# S7CAS-PLEIADES-CARTE-MERE_Pxx_PHY.net
KiCad netlist of a schematic drawn in Altium Designer
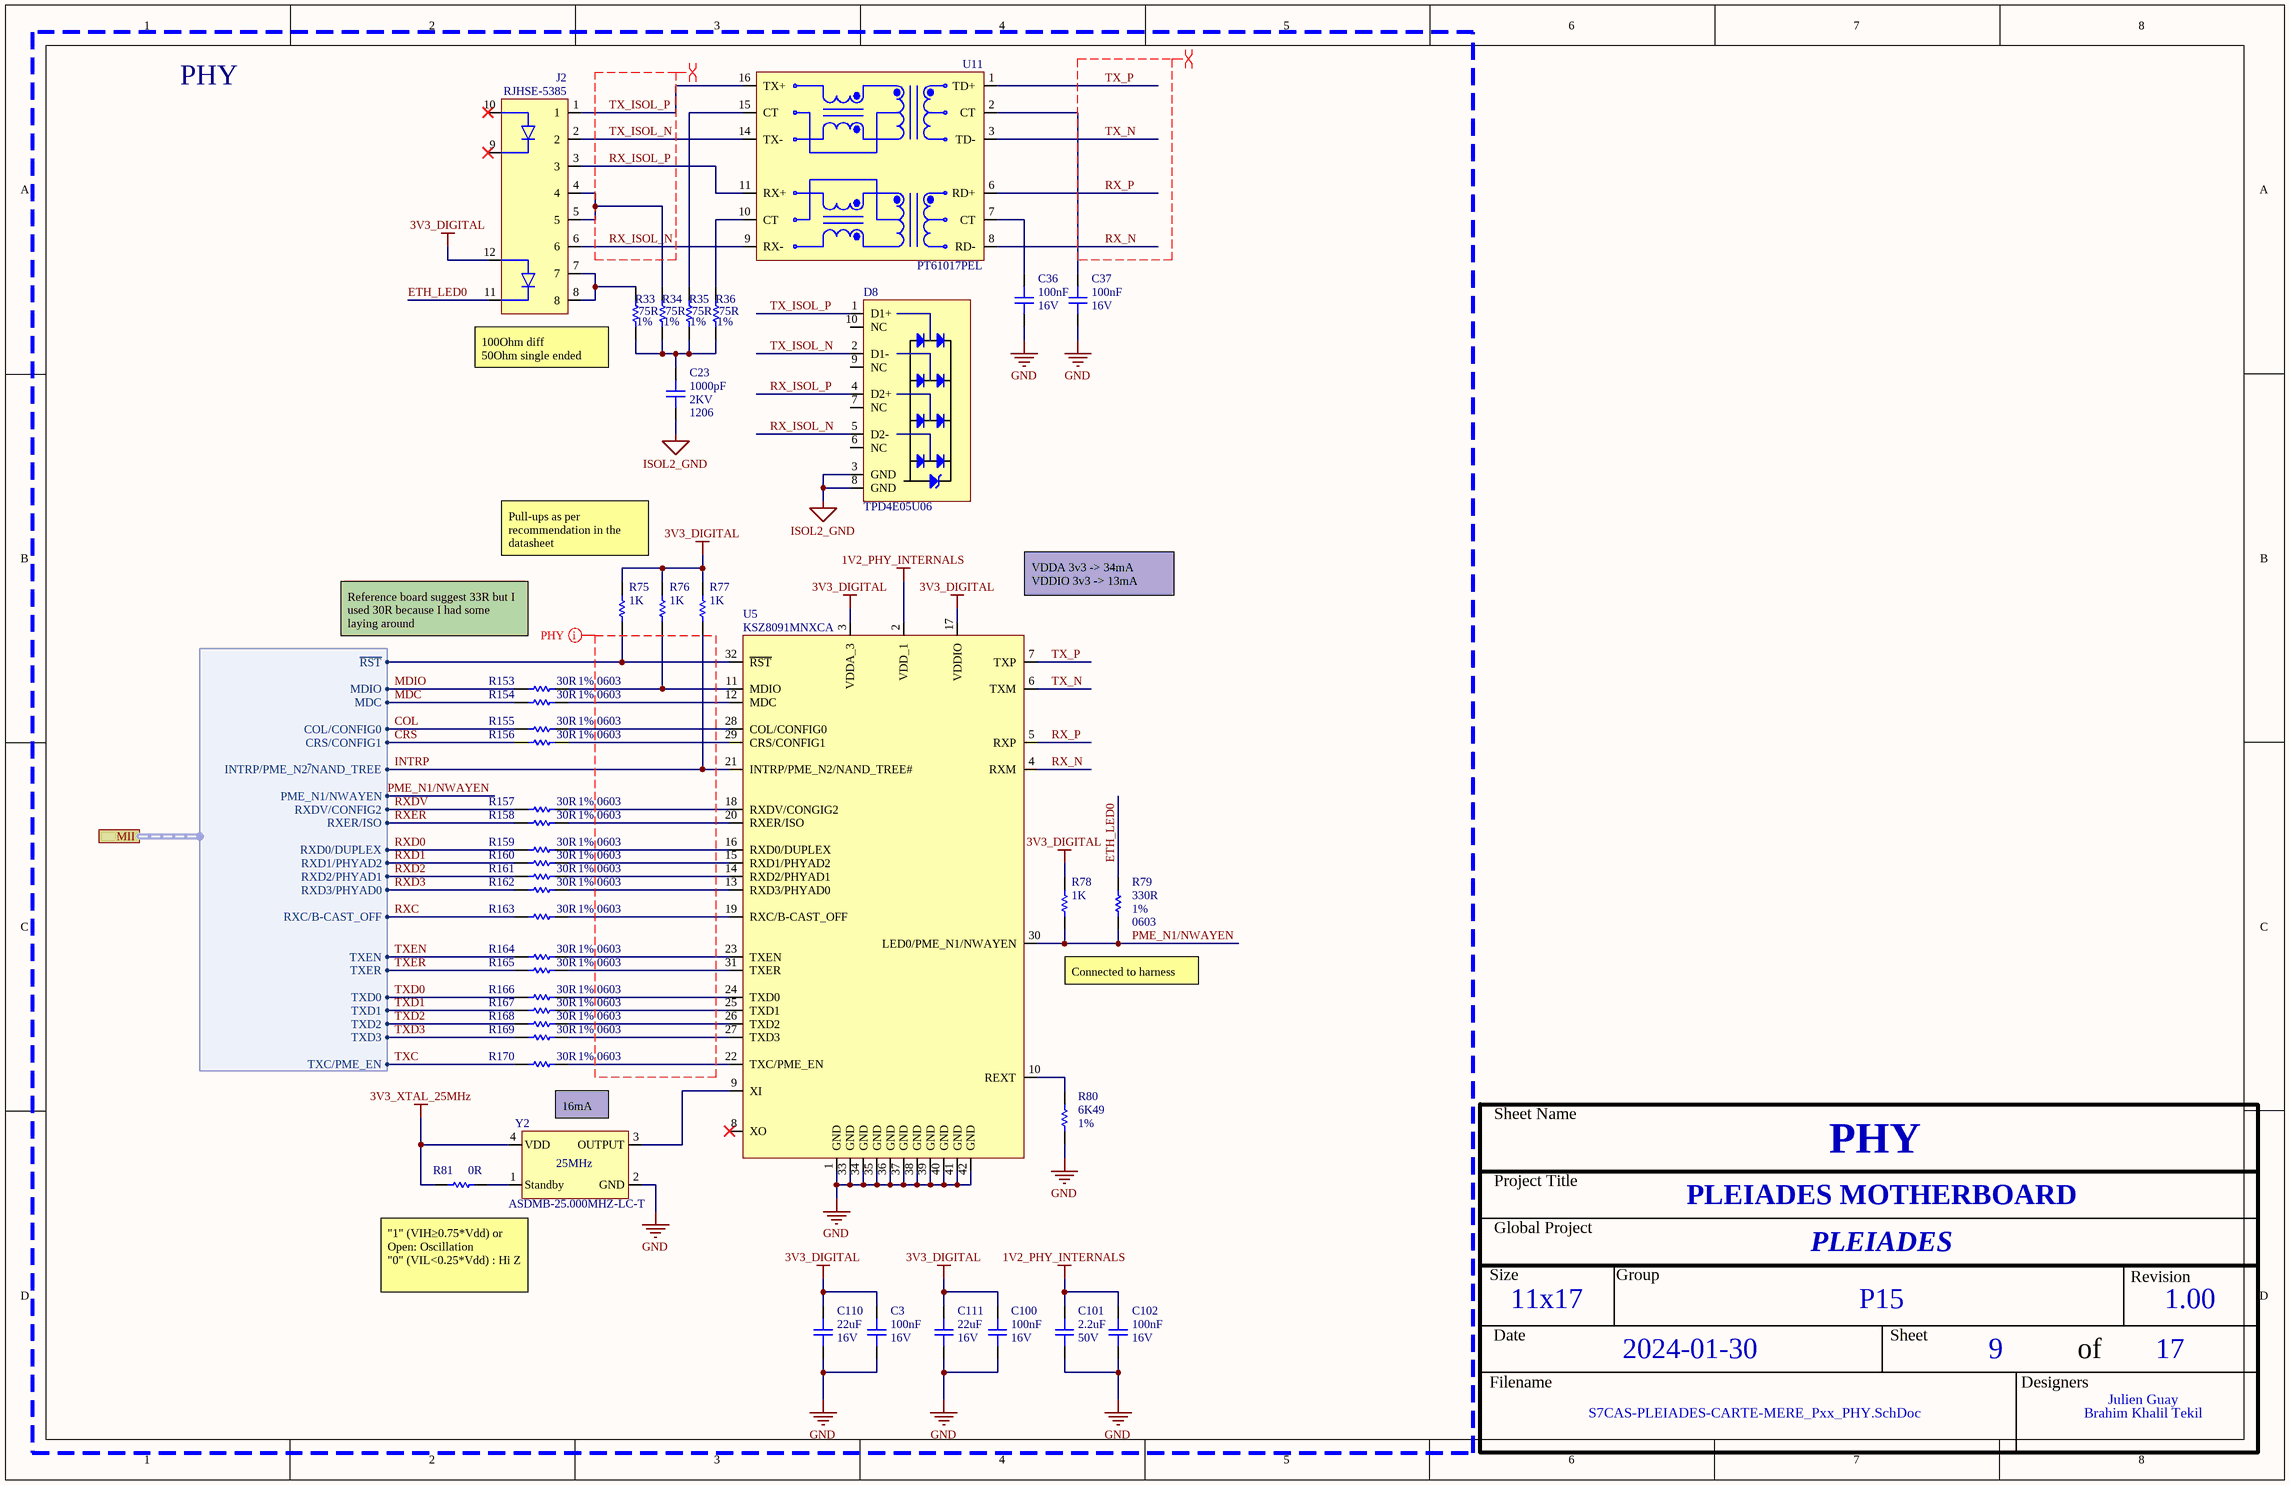
[diagram p0: S7CAS-PLEIADES-CARTE-MERE_Pxx_PHY.SchDoc]

(export (version "E")
  (design (tool "Eeschema 10.0.6"))
  (components
    (comp (ref "C3")
      (value "100nF")
      (footprint "CAP_0603")
      (description "CAP - 0603")
      (fields (field (name "VOLTAGE") "16V") (field (name "CREATEDBY") "Jonathan Bouchard"))
      (libsource (lib "S7CAS_LIB2023") (part "CAP - 0603"))
    )
    (comp (ref "C23")
      (value "1000pF")
      (footprint "CAP_1206")
      (description "CAP - 1206")
      (fields
        (field (name "VOLTAGE") "2KV")
        (field (name "PACKAGE") "1206")
        (field (name "CREATEDBY") "Jonathan Bouchard")
      )
      (libsource (lib "S7CAS_LIB2023") (part "CAP - 1206"))
    )
    (comp (ref "C36")
      (value "100nF")
      (footprint "CAP_0603")
      (description "CAP - 0603")
      (fields (field (name "VOLTAGE") "16V") (field (name "CREATEDBY") "Jonathan Bouchard"))
      (libsource (lib "S7CAS_LIB2023") (part "CAP - 0603"))
    )
    (comp (ref "C37")
      (value "100nF")
      (footprint "CAP_0603")
      (description "CAP - 0603")
      (fields (field (name "VOLTAGE") "16V") (field (name "CREATEDBY") "Jonathan Bouchard"))
      (libsource (lib "S7CAS_LIB2023") (part "CAP - 0603"))
    )
    (comp (ref "C100")
      (value "100nF")
      (footprint "CAP_0603")
      (description "CAP - 0603")
      (fields (field (name "VOLTAGE") "16V") (field (name "CREATEDBY") "Jonathan Bouchard"))
      (libsource (lib "S7CAS_LIB2023") (part "CAP - 0603"))
    )
    (comp (ref "C101")
      (value "2.2uF")
      (footprint "CAP_0603")
      (description "CAP - 0603")
      (fields (field (name "VOLTAGE") "50V") (field (name "CREATEDBY") "Jonathan Bouchard"))
      (libsource (lib "S7CAS_LIB2023") (part "CAP - 0603"))
    )
    (comp (ref "C102")
      (value "100nF")
      (footprint "CAP_0603")
      (description "CAP - 0603")
      (fields (field (name "VOLTAGE") "16V") (field (name "CREATEDBY") "Jonathan Bouchard"))
      (libsource (lib "S7CAS_LIB2023") (part "CAP - 0603"))
    )
    (comp (ref "C110")
      (value "22uF")
      (footprint "CAP_1206")
      (description "CAP - 1206")
      (fields (field (name "VOLTAGE") "16V") (field (name "CREATEDBY") "Jonathan Bouchard"))
      (libsource (lib "S7CAS_LIB2023") (part "CAP - 1206"))
    )
    (comp (ref "C111")
      (value "22uF")
      (footprint "CAP_1206")
      (description "CAP - 1206")
      (fields (field (name "VOLTAGE") "16V") (field (name "CREATEDBY") "Jonathan Bouchard"))
      (libsource (lib "S7CAS_LIB2023") (part "CAP - 1206"))
    )
    (comp (ref "D8")
      (value "TPD4E05U06")
      (footprint "TVS_DATA_TPD4E05U06")
      (description "TVS - TVS DIODE 5.5VWM 14VC - 10SON")
      (fields
        (field (name "CREATEDBY/DATE") "Olivier Bernard / 12/3/2018")
        (field (name "VERIFIEDBY") "Caroline Paulin / 4 juillet 2018")
      )
      (libsource (lib "S7CAS_LIB2023") (part "TVS_DATA_TPD4E05U06"))
    )
    (comp (ref "J2")
      (value "RJHSE-5385")
      (footprint "CONN_ETHERNET_RJHSE-5385")
      (description "CONN - MOD JACK RJ45 R/A ETHERNET - TH")
      (fields (field (name "MFG") "Amphenol") (field (name "CREATEDBY") "Jonathan Bouchard"))
      (libsource (lib "S7CAS_LIB2023") (part "CONN_ETHERNET_RJHSE-5385"))
    )
    (comp (ref "R33")
      (value "75R")
      (footprint "RES_0603")
      (description "RES - 0603")
      (fields (field (name "PRECISION") "1%") (field (name "CREATEDBY") "Jonathan Bouchard"))
      (libsource (lib "S7CAS_LIB2023") (part "RES - 0603"))
    )
    (comp (ref "R34")
      (value "75R")
      (footprint "RES_0603")
      (description "RES - 0603")
      (fields (field (name "PRECISION") "1%") (field (name "CREATEDBY") "Jonathan Bouchard"))
      (libsource (lib "S7CAS_LIB2023") (part "RES - 0603"))
    )
    (comp (ref "R35")
      (value "75R")
      (footprint "RES_0603")
      (description "RES - 0603")
      (fields (field (name "PRECISION") "1%") (field (name "CREATEDBY") "Jonathan Bouchard"))
      (libsource (lib "S7CAS_LIB2023") (part "RES - 0603"))
    )
    (comp (ref "R36")
      (value "75R")
      (footprint "RES_0603")
      (description "RES - 0603")
      (fields (field (name "PRECISION") "1%") (field (name "CREATEDBY") "Jonathan Bouchard"))
      (libsource (lib "S7CAS_LIB2023") (part "RES - 0603"))
    )
    (comp (ref "R75")
      (value "1K")
      (footprint "RES_0603")
      (description "RES - 0603")
      (fields (field (name "CREATEDBY") "Jonathan Bouchard"))
      (libsource (lib "S7CAS_LIB2023") (part "RES - 0603"))
    )
    (comp (ref "R76")
      (value "1K")
      (footprint "RES_0603")
      (description "RES - 0603")
      (fields (field (name "CREATEDBY") "Jonathan Bouchard"))
      (libsource (lib "S7CAS_LIB2023") (part "RES - 0603"))
    )
    (comp (ref "R77")
      (value "1K")
      (footprint "RES_0603")
      (description "RES - 0603")
      (fields (field (name "CREATEDBY") "Jonathan Bouchard"))
      (libsource (lib "S7CAS_LIB2023") (part "RES - 0603"))
    )
    (comp (ref "R78")
      (value "1K")
      (footprint "RES_0603")
      (description "RES - 0603")
      (fields (field (name "CREATEDBY") "Jonathan Bouchard"))
      (libsource (lib "S7CAS_LIB2023") (part "RES - 0603"))
    )
    (comp (ref "R79")
      (value "330R")
      (footprint "RES_0603")
      (description "RES - 0603")
      (fields
        (field (name "PACKAGE") "0603")
        (field (name "PRECISION") "1%")
        (field (name "CREATEDBY") "Jonathan Bouchard")
      )
      (libsource (lib "S7CAS_LIB2023") (part "RES - 0603"))
    )
    (comp (ref "R80")
      (value "6K49")
      (footprint "RES_0402")
      (description "RES - 0402")
      (fields
        (field (name "VOLTAGE") "50V")
        (field (name "POWER") "1/16W")
        (field (name "PRECISION") "1%")
        (field (name "CREATEDBY") "Jonathan Bouchard")
      )
      (libsource (lib "S7CAS_LIB2023") (part "RES - 0402"))
    )
    (comp (ref "R81")
      (value "0R")
      (footprint "RES_0603")
      (description "RES - 0603")
      (fields (field (name "CREATEDBY") "Jonathan Bouchard"))
      (libsource (lib "S7CAS_LIB2023") (part "RES - 0603"))
    )
    (comp (ref "R153")
      (value "30R")
      (footprint "RES_0603")
      (description "RES - 0603")
      (fields
        (field (name "PACKAGE") "0603")
        (field (name "PRECISION") "1%")
        (field (name "CREATEDBY") "Jonathan Bouchard")
      )
      (libsource (lib "S7CAS_LIB2023") (part "RES - 0603"))
    )
    (comp (ref "R154")
      (value "30R")
      (footprint "RES_0603")
      (description "RES - 0603")
      (fields
        (field (name "PACKAGE") "0603")
        (field (name "PRECISION") "1%")
        (field (name "CREATEDBY") "Jonathan Bouchard")
      )
      (libsource (lib "S7CAS_LIB2023") (part "RES - 0603"))
    )
    (comp (ref "R155")
      (value "30R")
      (footprint "RES_0603")
      (description "RES - 0603")
      (fields
        (field (name "PACKAGE") "0603")
        (field (name "PRECISION") "1%")
        (field (name "CREATEDBY") "Jonathan Bouchard")
      )
      (libsource (lib "S7CAS_LIB2023") (part "RES - 0603"))
    )
    (comp (ref "R156")
      (value "30R")
      (footprint "RES_0603")
      (description "RES - 0603")
      (fields
        (field (name "PACKAGE") "0603")
        (field (name "PRECISION") "1%")
        (field (name "CREATEDBY") "Jonathan Bouchard")
      )
      (libsource (lib "S7CAS_LIB2023") (part "RES - 0603"))
    )
    (comp (ref "R157")
      (value "30R")
      (footprint "RES_0603")
      (description "RES - 0603")
      (fields
        (field (name "PACKAGE") "0603")
        (field (name "PRECISION") "1%")
        (field (name "CREATEDBY") "Jonathan Bouchard")
      )
      (libsource (lib "S7CAS_LIB2023") (part "RES - 0603"))
    )
    (comp (ref "R158")
      (value "30R")
      (footprint "RES_0603")
      (description "RES - 0603")
      (fields
        (field (name "PACKAGE") "0603")
        (field (name "PRECISION") "1%")
        (field (name "CREATEDBY") "Jonathan Bouchard")
      )
      (libsource (lib "S7CAS_LIB2023") (part "RES - 0603"))
    )
    (comp (ref "R159")
      (value "30R")
      (footprint "RES_0603")
      (description "RES - 0603")
      (fields
        (field (name "PACKAGE") "0603")
        (field (name "PRECISION") "1%")
        (field (name "CREATEDBY") "Jonathan Bouchard")
      )
      (libsource (lib "S7CAS_LIB2023") (part "RES - 0603"))
    )
    (comp (ref "R160")
      (value "30R")
      (footprint "RES_0603")
      (description "RES - 0603")
      (fields
        (field (name "PACKAGE") "0603")
        (field (name "PRECISION") "1%")
        (field (name "CREATEDBY") "Jonathan Bouchard")
      )
      (libsource (lib "S7CAS_LIB2023") (part "RES - 0603"))
    )
    (comp (ref "R161")
      (value "30R")
      (footprint "RES_0603")
      (description "RES - 0603")
      (fields
        (field (name "PACKAGE") "0603")
        (field (name "PRECISION") "1%")
        (field (name "CREATEDBY") "Jonathan Bouchard")
      )
      (libsource (lib "S7CAS_LIB2023") (part "RES - 0603"))
    )
    (comp (ref "R162")
      (value "30R")
      (footprint "RES_0603")
      (description "RES - 0603")
      (fields
        (field (name "PACKAGE") "0603")
        (field (name "PRECISION") "1%")
        (field (name "CREATEDBY") "Jonathan Bouchard")
      )
      (libsource (lib "S7CAS_LIB2023") (part "RES - 0603"))
    )
    (comp (ref "R163")
      (value "30R")
      (footprint "RES_0603")
      (description "RES - 0603")
      (fields
        (field (name "PACKAGE") "0603")
        (field (name "PRECISION") "1%")
        (field (name "CREATEDBY") "Jonathan Bouchard")
      )
      (libsource (lib "S7CAS_LIB2023") (part "RES - 0603"))
    )
    (comp (ref "R164")
      (value "30R")
      (footprint "RES_0603")
      (description "RES - 0603")
      (fields
        (field (name "PACKAGE") "0603")
        (field (name "PRECISION") "1%")
        (field (name "CREATEDBY") "Jonathan Bouchard")
      )
      (libsource (lib "S7CAS_LIB2023") (part "RES - 0603"))
    )
    (comp (ref "R165")
      (value "30R")
      (footprint "RES_0603")
      (description "RES - 0603")
      (fields
        (field (name "PACKAGE") "0603")
        (field (name "PRECISION") "1%")
        (field (name "CREATEDBY") "Jonathan Bouchard")
      )
      (libsource (lib "S7CAS_LIB2023") (part "RES - 0603"))
    )
    (comp (ref "R166")
      (value "30R")
      (footprint "RES_0603")
      (description "RES - 0603")
      (fields
        (field (name "PACKAGE") "0603")
        (field (name "PRECISION") "1%")
        (field (name "CREATEDBY") "Jonathan Bouchard")
      )
      (libsource (lib "S7CAS_LIB2023") (part "RES - 0603"))
    )
    (comp (ref "R167")
      (value "30R")
      (footprint "RES_0603")
      (description "RES - 0603")
      (fields
        (field (name "PACKAGE") "0603")
        (field (name "PRECISION") "1%")
        (field (name "CREATEDBY") "Jonathan Bouchard")
      )
      (libsource (lib "S7CAS_LIB2023") (part "RES - 0603"))
    )
    (comp (ref "R168")
      (value "30R")
      (footprint "RES_0603")
      (description "RES - 0603")
      (fields
        (field (name "PACKAGE") "0603")
        (field (name "PRECISION") "1%")
        (field (name "CREATEDBY") "Jonathan Bouchard")
      )
      (libsource (lib "S7CAS_LIB2023") (part "RES - 0603"))
    )
    (comp (ref "R169")
      (value "30R")
      (footprint "RES_0603")
      (description "RES - 0603")
      (fields
        (field (name "PACKAGE") "0603")
        (field (name "PRECISION") "1%")
        (field (name "CREATEDBY") "Jonathan Bouchard")
      )
      (libsource (lib "S7CAS_LIB2023") (part "RES - 0603"))
    )
    (comp (ref "R170")
      (value "30R")
      (footprint "RES_0603")
      (description "RES - 0603")
      (fields
        (field (name "PACKAGE") "0603")
        (field (name "PRECISION") "1%")
        (field (name "CREATEDBY") "Jonathan Bouchard")
      )
      (libsource (lib "S7CAS_LIB2023") (part "RES - 0603"))
    )
    (comp (ref "U5")
      (value "KSZ8091MNXCA")
      (footprint "COM_ETH_PHY_KSZ8091MNXCA")
      (description "COM - ETHERNET PHY 10/100 - QFN-32")
      (fields
        (field (name "VOLTAGE") "1.8V, 2.5V, 3.3V")
        (field (name "MFG") "Micrel")
        (field (name "CREATEDBY") "Jonathan Bouchard")
      )
      (libsource (lib "S7CAS_LIB2023") (part "COM_ETH_PHY_KSZ8091MNXCA"))
    )
    (comp (ref "U11")
      (value "PT61017PEL")
      (footprint "ISO_PT61017PEL")
      (description "ISO - 350µH LAN 10/100 Base-T Pulse Transformer 1CT:1CT Surface Mount")
      (libsource (lib "S7CAS_LIB2023") (part "ISO_PT61017PEL"))
    )
    (comp (ref "Y2")
      (value "ASDMB-25.000MHZ-LC-T")
      (footprint "OSC_ASDMB-25.000MHZ-LC-T")
      (description "OSC - 25MHz XO (Standard) LVCMOS - 4-SMD, No Lead")
      (fields
        (field (name "TOLERANCE") "±50ppm")
        (field (name "CREATEDBY/DATE") "Joël Lemay 2019-03-29")
        (field (name "VERIFIEDBY") "C. Paulin - 29 mai 2019")
      )
      (libsource (lib "S7CAS_LIB2023") (part "OSC_ASDMB-25.000MHZ-LC-T"))
    )
  )
  (nets
    (net (code "4") (name "/COL") (class "Default")
      (node (ref "R155") (pin "1") (pinfunction "1_1") (pintype "passive"))
    )
    (net (code "5") (name "/CRS") (class "Default")
      (node (ref "R156") (pin "1") (pinfunction "1_1") (pintype "passive"))
    )
    (net (code "6") (name "/ETH_LED0") (class "Default")
      (node (ref "J2") (pin "11") (pinfunction "LED2_K_11") (pintype "passive"))
      (node (ref "R79") (pin "2") (pinfunction "2_2") (pintype "passive"))
    )
    (net (code "7") (name "/INTRP") (class "Default")
      (node (ref "R77") (pin "1") (pinfunction "1_1") (pintype "passive"))
      (node (ref "U5") (pin "21") (pinfunction "INTRP/PME_N2/NAND_TREE#_21") (pintype "passive"))
    )
    (net (code "8") (name "/MDC") (class "Default")
      (node (ref "R154") (pin "1") (pinfunction "1_1") (pintype "passive"))
    )
    (net (code "9") (name "/MDIO") (class "Default")
      (node (ref "R153") (pin "1") (pinfunction "1_1") (pintype "passive"))
    )
    (net (code "10") (name "/PME_N1{slash}NWAYEN") (class "Default")
      (node (ref "R78") (pin "1") (pinfunction "1_1") (pintype "passive"))
      (node (ref "R79") (pin "1") (pinfunction "1_1") (pintype "passive"))
      (node (ref "U5") (pin "30") (pinfunction "LED0/PME_N1/NWAYEN_30") (pintype "passive"))
    )
    (net (code "11") (name "/RXC") (class "Default")
      (node (ref "R163") (pin "1") (pinfunction "1_1") (pintype "passive"))
    )
    (net (code "12") (name "/RXD0") (class "Default")
      (node (ref "R159") (pin "1") (pinfunction "1_1") (pintype "passive"))
    )
    (net (code "13") (name "/RXD1") (class "Default")
      (node (ref "R160") (pin "1") (pinfunction "1_1") (pintype "passive"))
    )
    (net (code "14") (name "/RXD2") (class "Default")
      (node (ref "R161") (pin "1") (pinfunction "1_1") (pintype "passive"))
    )
    (net (code "15") (name "/RXD3") (class "Default")
      (node (ref "R162") (pin "1") (pinfunction "1_1") (pintype "passive"))
    )
    (net (code "16") (name "/RXDV") (class "Default")
      (node (ref "R157") (pin "1") (pinfunction "1_1") (pintype "passive"))
    )
    (net (code "17") (name "/RXER") (class "Default")
      (node (ref "R158") (pin "1") (pinfunction "1_1") (pintype "passive"))
    )
    (net (code "18") (name "/RX_ISOL_N") (class "Default")
      (node (ref "D8") (pin "5") (pinfunction "D2-_5") (pintype "passive"))
      (node (ref "J2") (pin "6") (pinfunction "6_6") (pintype "passive"))
      (node (ref "U11") (pin "9") (pinfunction "RX-_9") (pintype "passive"))
    )
    (net (code "19") (name "/RX_ISOL_P") (class "Default")
      (node (ref "D8") (pin "4") (pinfunction "D2+_4") (pintype "passive"))
      (node (ref "J2") (pin "3") (pinfunction "3_3") (pintype "passive"))
      (node (ref "U11") (pin "11") (pinfunction "RX+_11") (pintype "passive"))
    )
    (net (code "20") (name "/RX_N") (class "Default")
      (node (ref "U11") (pin "8") (pinfunction "RD-_8") (pintype "passive"))
      (node (ref "U5") (pin "4") (pinfunction "RXM_4") (pintype "passive"))
    )
    (net (code "21") (name "/RX_P") (class "Default")
      (node (ref "U11") (pin "6") (pinfunction "RD+_6") (pintype "passive"))
      (node (ref "U5") (pin "5") (pinfunction "RXP_5") (pintype "passive"))
    )
    (net (code "22") (name "/TXC") (class "Default")
      (node (ref "R170") (pin "1") (pinfunction "1_1") (pintype "passive"))
    )
    (net (code "23") (name "/TXD0") (class "Default")
      (node (ref "R166") (pin "1") (pinfunction "1_1") (pintype "passive"))
    )
    (net (code "24") (name "/TXD1") (class "Default")
      (node (ref "R167") (pin "1") (pinfunction "1_1") (pintype "passive"))
    )
    (net (code "25") (name "/TXD2") (class "Default")
      (node (ref "R168") (pin "1") (pinfunction "1_1") (pintype "passive"))
    )
    (net (code "26") (name "/TXD3") (class "Default")
      (node (ref "R169") (pin "1") (pinfunction "1_1") (pintype "passive"))
    )
    (net (code "27") (name "/TXEN") (class "Default")
      (node (ref "R164") (pin "1") (pinfunction "1_1") (pintype "passive"))
    )
    (net (code "28") (name "/TXER") (class "Default")
      (node (ref "R165") (pin "1") (pinfunction "1_1") (pintype "passive"))
    )
    (net (code "29") (name "/TX_ISOL_N") (class "Default")
      (node (ref "D8") (pin "2") (pinfunction "D1-_2") (pintype "passive"))
      (node (ref "J2") (pin "2") (pinfunction "2_2") (pintype "passive"))
      (node (ref "U11") (pin "14") (pinfunction "TX-_14") (pintype "passive"))
    )
    (net (code "30") (name "/TX_ISOL_P") (class "Default")
      (node (ref "D8") (pin "1") (pinfunction "D1+_1") (pintype "passive"))
      (node (ref "J2") (pin "1") (pinfunction "1_1") (pintype "passive"))
      (node (ref "U11") (pin "16") (pinfunction "TX+_16") (pintype "passive"))
    )
    (net (code "31") (name "/TX_N") (class "Default")
      (node (ref "U11") (pin "3") (pinfunction "TD-_3") (pintype "passive"))
      (node (ref "U5") (pin "6") (pinfunction "TXM_6") (pintype "passive"))
    )
    (net (code "32") (name "/TX_P") (class "Default")
      (node (ref "U11") (pin "1") (pinfunction "TD+_1") (pintype "passive"))
      (node (ref "U5") (pin "7") (pinfunction "TXP_7") (pintype "passive"))
    )
    (net (code "34") (name "1V2_PHY_INTERNALS") (class "Default")
      (node (ref "C101") (pin "2") (pinfunction "2_2") (pintype "passive"))
      (node (ref "C102") (pin "2") (pinfunction "2_2") (pintype "passive"))
      (node (ref "U5") (pin "2") (pinfunction "VDD_1_2") (pintype "power_in"))
    )
    (net (code "35") (name "3V3_DIGITAL") (class "Default")
      (node (ref "C100") (pin "2") (pinfunction "2_2") (pintype "passive"))
      (node (ref "C110") (pin "2") (pinfunction "2_2") (pintype "passive"))
      (node (ref "C111") (pin "2") (pinfunction "2_2") (pintype "passive"))
      (node (ref "C3") (pin "2") (pinfunction "2_2") (pintype "passive"))
      (node (ref "J2") (pin "12") (pinfunction "LED2_A_12") (pintype "passive"))
      (node (ref "R75") (pin "2") (pinfunction "2_2") (pintype "passive"))
      (node (ref "R76") (pin "2") (pinfunction "2_2") (pintype "passive"))
      (node (ref "R77") (pin "2") (pinfunction "2_2") (pintype "passive"))
      (node (ref "R78") (pin "2") (pinfunction "2_2") (pintype "passive"))
      (node (ref "U5") (pin "17") (pinfunction "VDDIO_17") (pintype "power_in"))
      (node (ref "U5") (pin "3") (pinfunction "VDDA_3_3") (pintype "power_in"))
    )
    (net (code "36") (name "3V3_XTAL_25MHz") (class "Default")
      (node (ref "R81") (pin "2") (pinfunction "2_2") (pintype "passive"))
      (node (ref "Y2") (pin "4") (pinfunction "VDD_4") (pintype "passive"))
    )
    (net (code "37") (name "GND") (class "Default")
      (node (ref "C100") (pin "1") (pinfunction "1_1") (pintype "passive"))
      (node (ref "C101") (pin "1") (pinfunction "1_1") (pintype "passive"))
      (node (ref "C102") (pin "1") (pinfunction "1_1") (pintype "passive"))
      (node (ref "C110") (pin "1") (pinfunction "1_1") (pintype "passive"))
      (node (ref "C111") (pin "1") (pinfunction "1_1") (pintype "passive"))
      (node (ref "C3") (pin "1") (pinfunction "1_1") (pintype "passive"))
      (node (ref "C36") (pin "1") (pinfunction "1_1") (pintype "passive"))
      (node (ref "C37") (pin "1") (pinfunction "1_1") (pintype "passive"))
      (node (ref "R80") (pin "1") (pinfunction "1_1") (pintype "passive"))
      (node (ref "U5") (pin "1") (pinfunction "GND_1") (pintype "passive"))
      (node (ref "U5") (pin "33") (pinfunction "GND_33") (pintype "passive"))
      (node (ref "U5") (pin "34") (pinfunction "GND_34") (pintype "passive"))
      (node (ref "U5") (pin "35") (pinfunction "GND_35") (pintype "passive"))
      (node (ref "U5") (pin "36") (pinfunction "GND_36") (pintype "passive"))
      (node (ref "U5") (pin "37") (pinfunction "GND_37") (pintype "passive"))
      (node (ref "U5") (pin "38") (pinfunction "GND_38") (pintype "passive"))
      (node (ref "U5") (pin "39") (pinfunction "GND_39") (pintype "passive"))
      (node (ref "U5") (pin "40") (pinfunction "GND_40") (pintype "passive"))
      (node (ref "U5") (pin "41") (pinfunction "GND_41") (pintype "passive"))
      (node (ref "U5") (pin "42") (pinfunction "GND_42") (pintype "passive"))
      (node (ref "Y2") (pin "2") (pinfunction "GND_2") (pintype "passive"))
    )
    (net (code "38") (name "ISOL2_GND") (class "Default")
      (node (ref "C23") (pin "1") (pinfunction "1_1") (pintype "passive"))
      (node (ref "D8") (pin "3") (pinfunction "GND_3") (pintype "passive"))
      (node (ref "D8") (pin "8") (pinfunction "GND_8") (pintype "passive"))
    )
    (net (code "39") (name "Net-(C23-Pad2)") (class "Default")
      (node (ref "C23") (pin "2") (pinfunction "2_2") (pintype "passive"))
      (node (ref "R33") (pin "1") (pinfunction "1_1") (pintype "passive"))
      (node (ref "R34") (pin "1") (pinfunction "1_1") (pintype "passive"))
      (node (ref "R35") (pin "1") (pinfunction "1_1") (pintype "passive"))
      (node (ref "R36") (pin "1") (pinfunction "1_1") (pintype "passive"))
    )
    (net (code "40") (name "Net-(C36-Pad2)") (class "Default")
      (node (ref "C36") (pin "2") (pinfunction "2_2") (pintype "passive"))
      (node (ref "U11") (pin "7") (pinfunction "CT_7") (pintype "passive"))
    )
    (net (code "41") (name "Net-(C37-Pad2)") (class "Default")
      (node (ref "C37") (pin "2") (pinfunction "2_2") (pintype "passive"))
      (node (ref "U11") (pin "2") (pinfunction "CT_2") (pintype "passive"))
    )
    (net (code "42") (name "Net-(J2-Pad4)") (class "Default")
      (node (ref "J2") (pin "4") (pinfunction "4_4") (pintype "passive"))
      (node (ref "J2") (pin "5") (pinfunction "5_5") (pintype "passive"))
      (node (ref "R34") (pin "2") (pinfunction "2_2") (pintype "passive"))
    )
    (net (code "43") (name "Net-(J2-Pad7)") (class "Default")
      (node (ref "J2") (pin "7") (pinfunction "7_7") (pintype "passive"))
      (node (ref "J2") (pin "8") (pinfunction "8_8") (pintype "passive"))
      (node (ref "R33") (pin "2") (pinfunction "2_2") (pintype "passive"))
    )
    (net (code "44") (name "Net-(R35-Pad2)") (class "Default")
      (node (ref "R35") (pin "2") (pinfunction "2_2") (pintype "passive"))
      (node (ref "U11") (pin "15") (pinfunction "CT_15") (pintype "passive"))
    )
    (net (code "45") (name "Net-(R36-Pad2)") (class "Default")
      (node (ref "R36") (pin "2") (pinfunction "2_2") (pintype "passive"))
      (node (ref "U11") (pin "10") (pinfunction "CT_10") (pintype "passive"))
    )
    (net (code "46") (name "Net-(U5-COL{slash}CONFIG0)") (class "Default")
      (node (ref "R155") (pin "2") (pinfunction "2_2") (pintype "passive"))
      (node (ref "U5") (pin "28") (pinfunction "COL/CONFIG0_28") (pintype "passive"))
    )
    (net (code "47") (name "Net-(U5-CRS{slash}CONFIG1)") (class "Default")
      (node (ref "R156") (pin "2") (pinfunction "2_2") (pintype "passive"))
      (node (ref "U5") (pin "29") (pinfunction "CRS/CONFIG1_29") (pintype "passive"))
    )
    (net (code "48") (name "Net-(U5-MDC)") (class "Default")
      (node (ref "R154") (pin "2") (pinfunction "2_2") (pintype "passive"))
      (node (ref "U5") (pin "12") (pinfunction "MDC_12") (pintype "passive"))
    )
    (net (code "49") (name "Net-(U5-MDIO)") (class "Default")
      (node (ref "R153") (pin "2") (pinfunction "2_2") (pintype "passive"))
      (node (ref "R76") (pin "1") (pinfunction "1_1") (pintype "passive"))
      (node (ref "U5") (pin "11") (pinfunction "MDIO_11") (pintype "passive"))
    )
    (net (code "50") (name "Net-(U5-REXT)") (class "Default")
      (node (ref "R80") (pin "2") (pinfunction "2_2") (pintype "passive"))
      (node (ref "U5") (pin "10") (pinfunction "REXT_10") (pintype "passive"))
    )
    (net (code "51") (name "Net-(U5-RST)") (class "Default")
      (node (ref "R75") (pin "1") (pinfunction "1_1") (pintype "passive"))
      (node (ref "U5") (pin "32") (pinfunction "RST_32") (pintype "passive"))
    )
    (net (code "52") (name "Net-(U5-RXC{slash}B-CAST_OFF)") (class "Default")
      (node (ref "R163") (pin "2") (pinfunction "2_2") (pintype "passive"))
      (node (ref "U5") (pin "19") (pinfunction "RXC/B-CAST_OFF_19") (pintype "passive"))
    )
    (net (code "53") (name "Net-(U5-RXD0{slash}DUPLEX)") (class "Default")
      (node (ref "R159") (pin "2") (pinfunction "2_2") (pintype "passive"))
      (node (ref "U5") (pin "16") (pinfunction "RXD0/DUPLEX_16") (pintype "passive"))
    )
    (net (code "54") (name "Net-(U5-RXD1{slash}PHYAD2)") (class "Default")
      (node (ref "R160") (pin "2") (pinfunction "2_2") (pintype "passive"))
      (node (ref "U5") (pin "15") (pinfunction "RXD1/PHYAD2_15") (pintype "passive"))
    )
    (net (code "55") (name "Net-(U5-RXD2{slash}PHYAD1)") (class "Default")
      (node (ref "R161") (pin "2") (pinfunction "2_2") (pintype "passive"))
      (node (ref "U5") (pin "14") (pinfunction "RXD2/PHYAD1_14") (pintype "passive"))
    )
    (net (code "56") (name "Net-(U5-RXD3{slash}PHYAD0)") (class "Default")
      (node (ref "R162") (pin "2") (pinfunction "2_2") (pintype "passive"))
      (node (ref "U5") (pin "13") (pinfunction "RXD3/PHYAD0_13") (pintype "passive"))
    )
    (net (code "57") (name "Net-(U5-RXDV{slash}CONGIG2)") (class "Default")
      (node (ref "R157") (pin "2") (pinfunction "2_2") (pintype "passive"))
      (node (ref "U5") (pin "18") (pinfunction "RXDV/CONGIG2_18") (pintype "passive"))
    )
    (net (code "58") (name "Net-(U5-RXER{slash}ISO)") (class "Default")
      (node (ref "R158") (pin "2") (pinfunction "2_2") (pintype "passive"))
      (node (ref "U5") (pin "20") (pinfunction "RXER/ISO_20") (pintype "passive"))
    )
    (net (code "59") (name "Net-(U5-TXC{slash}PME_EN)") (class "Default")
      (node (ref "R170") (pin "2") (pinfunction "2_2") (pintype "passive"))
      (node (ref "U5") (pin "22") (pinfunction "TXC/PME_EN_22") (pintype "passive"))
    )
    (net (code "60") (name "Net-(U5-TXD0)") (class "Default")
      (node (ref "R166") (pin "2") (pinfunction "2_2") (pintype "passive"))
      (node (ref "U5") (pin "24") (pinfunction "TXD0_24") (pintype "passive"))
    )
    (net (code "61") (name "Net-(U5-TXD1)") (class "Default")
      (node (ref "R167") (pin "2") (pinfunction "2_2") (pintype "passive"))
      (node (ref "U5") (pin "25") (pinfunction "TXD1_25") (pintype "passive"))
    )
    (net (code "62") (name "Net-(U5-TXD2)") (class "Default")
      (node (ref "R168") (pin "2") (pinfunction "2_2") (pintype "passive"))
      (node (ref "U5") (pin "26") (pinfunction "TXD2_26") (pintype "passive"))
    )
    (net (code "63") (name "Net-(U5-TXD3)") (class "Default")
      (node (ref "R169") (pin "2") (pinfunction "2_2") (pintype "passive"))
      (node (ref "U5") (pin "27") (pinfunction "TXD3_27") (pintype "passive"))
    )
    (net (code "64") (name "Net-(U5-TXEN)") (class "Default")
      (node (ref "R164") (pin "2") (pinfunction "2_2") (pintype "passive"))
      (node (ref "U5") (pin "23") (pinfunction "TXEN_23") (pintype "passive"))
    )
    (net (code "65") (name "Net-(U5-TXER)") (class "Default")
      (node (ref "R165") (pin "2") (pinfunction "2_2") (pintype "passive"))
      (node (ref "U5") (pin "31") (pinfunction "TXER_31") (pintype "passive"))
    )
    (net (code "66") (name "Net-(U5-XI)") (class "Default")
      (node (ref "U5") (pin "9") (pinfunction "XI_9") (pintype "passive"))
      (node (ref "Y2") (pin "3") (pinfunction "OUTPUT_3") (pintype "passive"))
    )
    (net (code "67") (name "Net-(Y2-Standby)") (class "Default")
      (node (ref "R81") (pin "1") (pinfunction "1_1") (pintype "passive"))
      (node (ref "Y2") (pin "1") (pinfunction "Standby_1") (pintype "passive"))
    )
    (net (code "68") (name "unconnected-(D8-NC-Pad6)") (class "Default")
      (node (ref "D8") (pin "6") (pinfunction "NC_6") (pintype "passive"))
    )
    (net (code "69") (name "unconnected-(D8-NC-Pad7)") (class "Default")
      (node (ref "D8") (pin "7") (pinfunction "NC_7") (pintype "passive"))
    )
    (net (code "70") (name "unconnected-(D8-NC-Pad9)") (class "Default")
      (node (ref "D8") (pin "9") (pinfunction "NC_9") (pintype "passive"))
    )
    (net (code "71") (name "unconnected-(D8-NC-Pad10)") (class "Default")
      (node (ref "D8") (pin "10") (pinfunction "NC_10") (pintype "passive"))
    )
    (net (code "72") (name "unconnected-(J2-LED1_A-Pad10)") (class "Default")
      (node (ref "J2") (pin "10") (pinfunction "LED1_A_10") (pintype "passive+no_connect"))
    )
    (net (code "73") (name "unconnected-(J2-LED1_K-Pad9)") (class "Default")
      (node (ref "J2") (pin "9") (pinfunction "LED1_K_9") (pintype "passive+no_connect"))
    )
    (net (code "74") (name "unconnected-(U5-XO-Pad8)") (class "Default")
      (node (ref "U5") (pin "8") (pinfunction "XO_8") (pintype "passive+no_connect"))
    )
  )
)
